# NMX-201.net
KiCad netlist of a schematic drawn in EAGLE
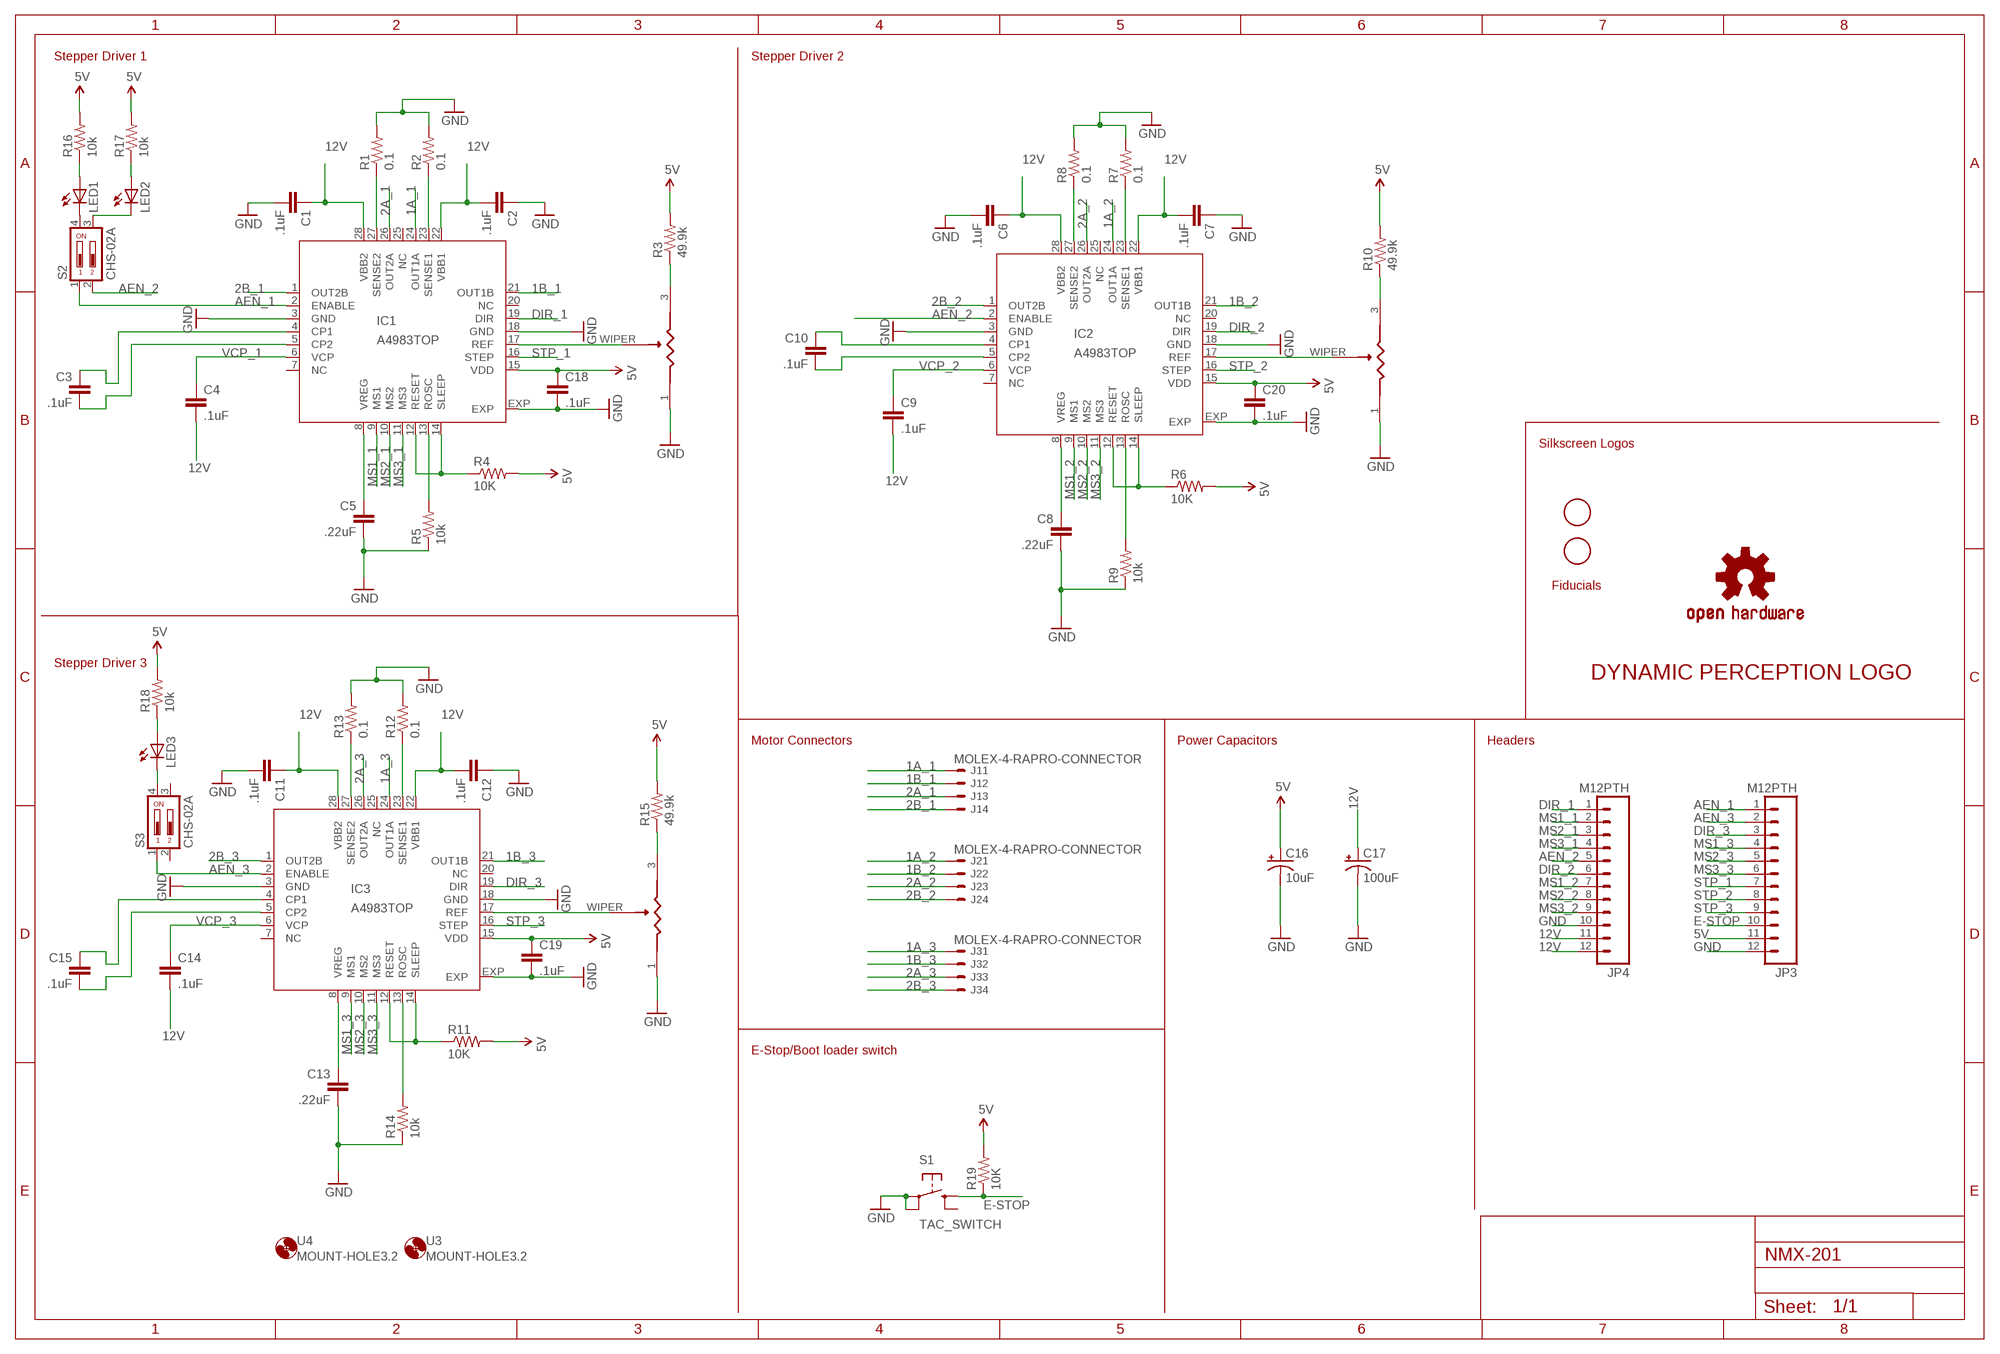
[diagram p0: schematic, sheet 1]

(export (version "E")
  (design (tool "Eeschema 10.0.6"))
  (components
    (comp (ref "C1")
      (value ".1uF")
      (footprint "eagle-import:0402-CAP")
      (fields (field (name "MF") "Taiyo Yuden") (field (name "MPN") "TMK105BJ104KV-F"))
      (libsource (lib "eagle-import") (part "CAP0402-CAP"))
    )
    (comp (ref "C2")
      (value ".1uF")
      (footprint "eagle-import:0402-CAP")
      (fields (field (name "MF") "Taiyo Yuden") (field (name "MPN") "TMK105BJ104KV-F"))
      (libsource (lib "eagle-import") (part "CAP0402-CAP"))
    )
    (comp (ref "C3")
      (value ".1uF")
      (footprint "eagle-import:0402-CAP")
      (fields (field (name "MF") "Taiyo Yuden") (field (name "MPN") "TMK105BJ104KV-F"))
      (libsource (lib "eagle-import") (part "CAP0402-CAP"))
    )
    (comp (ref "C4")
      (value ".1uF")
      (footprint "eagle-import:0402-CAP")
      (fields (field (name "MF") "Taiyo Yuden") (field (name "MPN") "TMK105BJ104KV-F"))
      (libsource (lib "eagle-import") (part "CAP0402-CAP"))
    )
    (comp (ref "C5")
      (value ".22uF")
      (footprint "eagle-import:0402-CAP")
      (fields (field (name "MF") "Taiyo Yuden") (field (name "MPN") "TMK105BJ224KVHF"))
      (libsource (lib "eagle-import") (part "CAP0402-CAP"))
    )
    (comp (ref "C6")
      (value ".1uF")
      (footprint "eagle-import:0402-CAP")
      (fields (field (name "MF") "Taiyo Yuden") (field (name "MPN") "TMK105BJ104KV-F"))
      (libsource (lib "eagle-import") (part "CAP0402-CAP"))
    )
    (comp (ref "C7")
      (value ".1uF")
      (footprint "eagle-import:0402-CAP")
      (fields (field (name "MF") "Taiyo Yuden") (field (name "MPN") "TMK105BJ104KV-F"))
      (libsource (lib "eagle-import") (part "CAP0402-CAP"))
    )
    (comp (ref "C8")
      (value ".22uF")
      (footprint "eagle-import:0402-CAP")
      (fields (field (name "MF") "Taiyo Yuden") (field (name "MPN") "TMK105BJ224KVHF"))
      (libsource (lib "eagle-import") (part "CAP0402-CAP"))
    )
    (comp (ref "C9")
      (value ".1uF")
      (footprint "eagle-import:0402-CAP")
      (fields (field (name "MF") "Taiyo Yuden") (field (name "MPN") "TMK105BJ104KV-F"))
      (libsource (lib "eagle-import") (part "CAP0402-CAP"))
    )
    (comp (ref "C10")
      (value ".1uF")
      (footprint "eagle-import:0402-CAP")
      (fields (field (name "MF") "Taiyo Yuden") (field (name "MPN") "TMK105BJ104KV-F"))
      (libsource (lib "eagle-import") (part "CAP0402-CAP"))
    )
    (comp (ref "C11")
      (value ".1uF")
      (footprint "eagle-import:0402-CAP")
      (fields (field (name "MF") "Taiyo Yuden") (field (name "MPN") "TMK105BJ104KV-F"))
      (libsource (lib "eagle-import") (part "CAP0402-CAP"))
    )
    (comp (ref "C12")
      (value ".1uF")
      (footprint "eagle-import:0402-CAP")
      (fields (field (name "MF") "Taiyo Yuden") (field (name "MPN") "TMK105BJ104KV-F"))
      (libsource (lib "eagle-import") (part "CAP0402-CAP"))
    )
    (comp (ref "C13")
      (value ".22uF")
      (footprint "eagle-import:0402-CAP")
      (fields (field (name "MF") "Taiyo Yuden") (field (name "MPN") "TMK105BJ224KVHF"))
      (libsource (lib "eagle-import") (part "CAP0402-CAP"))
    )
    (comp (ref "C14")
      (value ".1uF")
      (footprint "eagle-import:0402-CAP")
      (fields (field (name "MF") "Taiyo Yuden") (field (name "MPN") "TMK105BJ104KV-F"))
      (libsource (lib "eagle-import") (part "CAP0402-CAP"))
    )
    (comp (ref "C15")
      (value ".1uF")
      (footprint "eagle-import:0402-CAP")
      (fields (field (name "MF") "Taiyo Yuden") (field (name "MPN") "TMK105BJ104KV-F"))
      (libsource (lib "eagle-import") (part "CAP0402-CAP"))
    )
    (comp (ref "C16")
      (value "10uF")
      (footprint "eagle-import:EIA3216")
      (fields (field (name "MF") "Kemet") (field (name "MPN") "T491A106M016AT"))
      (libsource (lib "eagle-import") (part "CAP_POL1206"))
    )
    (comp (ref "C17")
      (value "100uF")
      (footprint "eagle-import:PANASONIC_D")
      (fields (field (name "MF") "Panasonic Electronic Components") (field (name "MPN") "EEE-1EA101XP"))
      (libsource (lib "eagle-import") (part "CAP_POLD"))
    )
    (comp (ref "C18")
      (value ".1uF")
      (footprint "eagle-import:0402-CAP")
      (fields (field (name "MF") "Taiyo Yuden") (field (name "MPN") "TMK105BJ104KV-F"))
      (libsource (lib "eagle-import") (part "CAP0402-CAP"))
    )
    (comp (ref "C19")
      (value ".1uF")
      (footprint "eagle-import:0402-CAP")
      (fields (field (name "MF") "Taiyo Yuden") (field (name "MPN") "TMK105BJ104KV-F"))
      (libsource (lib "eagle-import") (part "CAP0402-CAP"))
    )
    (comp (ref "C20")
      (value ".1uF")
      (footprint "eagle-import:0402-CAP")
      (fields (field (name "MF") "Taiyo Yuden") (field (name "MPN") "TMK105BJ104KV-F"))
      (libsource (lib "eagle-import") (part "CAP0402-CAP"))
    )
    (comp (ref "FRAME2")
      (value "A3L-LOCSILK_SCREEN")
      (footprint "eagle-import:DRAWING_NAME")
      (libsource (lib "eagle-import") (part "A3L-LOCSILK_SCREEN"))
    )
    (comp (ref "IC1")
      (value "A4983TOP")
      (footprint "eagle-import:QFN28ET")
      (fields (field (name "MPN") "A4983SETTR-T") (field (name "MPN_1") "A4983SETTR-T"))
      (libsource (lib "eagle-import") (part "A4983TOP"))
    )
    (comp (ref "IC2")
      (value "A4983TOP")
      (footprint "eagle-import:QFN28ET")
      (fields (field (name "MPN") "A4983SETTR-T") (field (name "MPN_1") "A4983SETTR-T"))
      (libsource (lib "eagle-import") (part "A4983TOP"))
    )
    (comp (ref "IC3")
      (value "A4983TOP")
      (footprint "eagle-import:QFN28ET")
      (fields (field (name "MPN") "A4983SETTR-T") (field (name "MPN_1") "A4983SETTR-T"))
      (libsource (lib "eagle-import") (part "A4983TOP"))
    )
    (comp (ref "J1")
      (value "MOLEX-4-RAPRO-CONNECTOR")
      (footprint "eagle-import:PRO_CONNECTOR")
      (fields (field (name "MF") "Molex Inc") (field (name "MPN") "0022053041"))
      (libsource (lib "eagle-import") (part "MOLEX-4-RAPRO-CONNECTOR"))
    )
    (comp (ref "J2")
      (value "MOLEX-4-RAPRO-CONNECTOR")
      (footprint "eagle-import:PRO_CONNECTOR")
      (fields (field (name "MF") "Molex Inc") (field (name "MPN") "0022053041"))
      (libsource (lib "eagle-import") (part "MOLEX-4-RAPRO-CONNECTOR"))
    )
    (comp (ref "J3")
      (value "MOLEX-4-RAPRO-CONNECTOR")
      (footprint "eagle-import:PRO_CONNECTOR")
      (fields (field (name "MF") "Molex Inc") (field (name "MPN") "0022053041"))
      (libsource (lib "eagle-import") (part "MOLEX-4-RAPRO-CONNECTOR"))
    )
    (comp (ref "JP3")
      (value "M12PTH")
      (footprint "eagle-import:1X12")
      (fields (field (name "MF") "Molex Inc") (field (name "MPN") "0901200132"))
      (libsource (lib "eagle-import") (part "M12PTH"))
    )
    (comp (ref "JP4")
      (value "M12PTH")
      (footprint "eagle-import:1X12")
      (fields (field (name "MF") "Molex Inc") (field (name "MPN") "0901200132"))
      (libsource (lib "eagle-import") (part "M12PTH"))
    )
    (comp (ref "LED1")
      (value "LED0603")
      (footprint "eagle-import:LED-0603")
      (fields (field (name "MF") "OSRAM Opto Semiconductors Inc") (field (name "MPN") "LB Q39G-L2N2-35-1"))
      (libsource (lib "eagle-import") (part "LED0603"))
    )
    (comp (ref "LED2")
      (value "LED0603")
      (footprint "eagle-import:LED-0603")
      (fields (field (name "MF") "OSRAM Opto Semiconductors Inc") (field (name "MPN") "LB Q39G-L2N2-35-1"))
      (libsource (lib "eagle-import") (part "LED0603"))
    )
    (comp (ref "LED3")
      (value "LED0603")
      (footprint "eagle-import:LED-0603")
      (fields (field (name "MF") "OSRAM Opto Semiconductors Inc") (field (name "MPN") "LB Q39G-L2N2-35-1"))
      (libsource (lib "eagle-import") (part "LED0603"))
    )
    (comp (ref "R1")
      (value "0.1")
      (footprint "eagle-import:R0603")
      (fields (field (name "MF") "Samsung Electro-Mechanics America") (field (name "MPN") "RU1608FR100CS"))
      (libsource (lib "eagle-import") (part "R-US_R0603"))
    )
    (comp (ref "R2")
      (value "0.1")
      (footprint "eagle-import:R0603")
      (fields (field (name "MF") "Samsung Electro-Mechanics America") (field (name "MPN") "RU1608FR100CS"))
      (libsource (lib "eagle-import") (part "R-US_R0603"))
    )
    (comp (ref "R3")
      (value "49.9k")
      (footprint "eagle-import:R0402_BOTTOM")
      (fields (field (name "MF") "Yageo") (field (name "MPN") "RC0402FR-0749K9L"))
      (libsource (lib "eagle-import") (part "R-US_R0402_B"))
    )
    (comp (ref "R4")
      (value "10K")
      (footprint "eagle-import:R0402_BOTTOM")
      (fields (field (name "MF") "Yageo") (field (name "MPN") "RC0402FR-0710KL"))
      (libsource (lib "eagle-import") (part "R-US_R0402_B"))
    )
    (comp (ref "R5")
      (value "10k")
      (footprint "eagle-import:R0402_BOTTOM")
      (fields (field (name "MF") "Yageo") (field (name "MPN") "RC0402FR-0720KL"))
      (libsource (lib "eagle-import") (part "R-US_R0402_B"))
    )
    (comp (ref "R6")
      (value "10K")
      (footprint "eagle-import:R0402_BOTTOM")
      (fields (field (name "MF") "Yageo") (field (name "MPN") "RC0402FR-0710KL"))
      (libsource (lib "eagle-import") (part "R-US_R0402_B"))
    )
    (comp (ref "R7")
      (value "0.1")
      (footprint "eagle-import:R0603")
      (fields (field (name "MF") "Samsung Electro-Mechanics America") (field (name "MPN") "RU1608FR100CS"))
      (libsource (lib "eagle-import") (part "R-US_R0603"))
    )
    (comp (ref "R8")
      (value "0.1")
      (footprint "eagle-import:R0603")
      (fields (field (name "MF") "Samsung Electro-Mechanics America") (field (name "MPN") "RU1608FR100CS"))
      (libsource (lib "eagle-import") (part "R-US_R0603"))
    )
    (comp (ref "R9")
      (value "10k")
      (footprint "eagle-import:R0402_BOTTOM")
      (fields (field (name "MF") "Yageo") (field (name "MPN") "RC0402FR-0720KL"))
      (libsource (lib "eagle-import") (part "R-US_R0402_B"))
    )
    (comp (ref "R10")
      (value "49.9k")
      (footprint "eagle-import:R0402_BOTTOM")
      (fields (field (name "MF") "Yageo") (field (name "MPN") "RC0402FR-0749K9L"))
      (libsource (lib "eagle-import") (part "R-US_R0402_B"))
    )
    (comp (ref "R11")
      (value "10K")
      (footprint "eagle-import:R0402_BOTTOM")
      (fields (field (name "MF") "Yageo") (field (name "MPN") "RC0402FR-0710KL"))
      (libsource (lib "eagle-import") (part "R-US_R0402_B"))
    )
    (comp (ref "R12")
      (value "0.1")
      (footprint "eagle-import:R0603")
      (fields (field (name "MF") "Samsung Electro-Mechanics America") (field (name "MPN") "RU1608FR100CS"))
      (libsource (lib "eagle-import") (part "R-US_R0603"))
    )
    (comp (ref "R13")
      (value "0.1")
      (footprint "eagle-import:R0603")
      (fields (field (name "MF") "Samsung Electro-Mechanics America") (field (name "MPN") "RU1608FR100CS"))
      (libsource (lib "eagle-import") (part "R-US_R0603"))
    )
    (comp (ref "R14")
      (value "10k")
      (footprint "eagle-import:R0402_BOTTOM")
      (fields (field (name "MF") "Yageo") (field (name "MPN") "RC0402FR-0720KL"))
      (libsource (lib "eagle-import") (part "R-US_R0402_B"))
    )
    (comp (ref "R15")
      (value "49.9k")
      (footprint "eagle-import:R0402_BOTTOM")
      (fields (field (name "MF") "Yageo") (field (name "MPN") "RC0402FR-0749K9L"))
      (libsource (lib "eagle-import") (part "R-US_R0402_B"))
    )
    (comp (ref "R16")
      (value "10k")
      (footprint "eagle-import:R0402_BOTTOM")
      (fields (field (name "MF") "Yageo") (field (name "MPN") "RC0402FR-0714KL"))
      (libsource (lib "eagle-import") (part "R-US_R0402_B"))
    )
    (comp (ref "R17")
      (value "10k")
      (footprint "eagle-import:R0402_BOTTOM")
      (fields (field (name "MF") "Yageo") (field (name "MPN") "RC0402FR-0714KL"))
      (libsource (lib "eagle-import") (part "R-US_R0402_B"))
    )
    (comp (ref "R18")
      (value "10k")
      (footprint "eagle-import:R0402_BOTTOM")
      (fields (field (name "MF") "Yageo") (field (name "MPN") "RC0402FR-0714KL"))
      (libsource (lib "eagle-import") (part "R-US_R0402_B"))
    )
    (comp (ref "R19")
      (value "10K")
      (footprint "eagle-import:R0402_BOTTOM")
      (fields (field (name "MF") "Yageo") (field (name "MPN") "RC0402FR-0710KL"))
      (libsource (lib "eagle-import") (part "R-US_R0402_B"))
    )
    (comp (ref "S1")
      (value "TAC_SWITCH")
      (footprint "eagle-import:TAC_SWITCH_THR")
      (fields (field (name "MF") "TE Connectivity") (field (name "MPN") "2-1825027-0"))
      (libsource (lib "eagle-import") (part "TAC_SWITCH"))
    )
    (comp (ref "S2")
      (value "CHS-02A")
      (footprint "eagle-import:CHS-02A")
      (libsource (lib "eagle-import") (part "CHS-02A"))
    )
    (comp (ref "S3")
      (value "CHS-02A")
      (footprint "eagle-import:CHS-02A")
      (libsource (lib "eagle-import") (part "CHS-02A"))
    )
    (comp (ref "U$1")
      (value "DP_LOGOMICRO")
      (footprint "eagle-import:DP_LOGO_MICRO")
      (libsource (lib "eagle-import") (part "DP_LOGOMICRO"))
    )
    (comp (ref "U$2")
      (value "OSHW-LOGOS")
      (footprint "eagle-import:OSHW-LOGO-S")
      (libsource (lib "eagle-import") (part "OSHW-LOGOS"))
    )
    (comp (ref "U$3")
      (value "FIDUCIAL")
      (footprint "eagle-import:FIDUCIAL_1MM")
      (libsource (lib "eagle-import") (part "FIDUCIAL"))
    )
    (comp (ref "U$4")
      (value "FIDUCIAL")
      (footprint "eagle-import:FIDUCIAL_1MM")
      (libsource (lib "eagle-import") (part "FIDUCIAL"))
    )
    (comp (ref "U1")
      (value "CADJ")
      (footprint "eagle-import:3MM_SMD")
      (fields (field (name "MF") "Bourns Inc") (field (name "MPN") "TC33X-2-103E"))
      (libsource (lib "eagle-import") (part "TC33X-2"))
    )
    (comp (ref "U2")
      (value "CADJ")
      (footprint "eagle-import:3MM_SMD")
      (fields (field (name "MF") "Bourns Inc") (field (name "MPN") "TC33X-2-103E"))
      (libsource (lib "eagle-import") (part "TC33X-2"))
    )
    (comp (ref "U3")
      (value "MOUNT-HOLE3.2")
      (footprint "eagle-import:3,2")
      (libsource (lib "eagle-import") (part "MOUNT-HOLE3.2"))
    )
    (comp (ref "U4")
      (value "MOUNT-HOLE3.2")
      (footprint "eagle-import:3,2")
      (libsource (lib "eagle-import") (part "MOUNT-HOLE3.2"))
    )
    (comp (ref "U5")
      (value "CADJ")
      (footprint "eagle-import:3MM_SMD")
      (fields (field (name "MF") "Bourns Inc") (field (name "MPN") "TC33X-2-103E"))
      (libsource (lib "eagle-import") (part "TC33X-2"))
    )
  )
  (nets
    (net (code "1") (name "/1A_1") (class "Default")
      (node (ref "IC1") (pin "24") (pinfunction "OUT1A_24") (pintype "output"))
      (node (ref "J1") (pin "P$1") (pinfunction "S_P$1") (pintype "passive"))
    )
    (net (code "2") (name "/1A_2") (class "Default")
      (node (ref "IC2") (pin "24") (pinfunction "OUT1A_24") (pintype "output"))
      (node (ref "J2") (pin "P$1") (pinfunction "S_P$1") (pintype "passive"))
    )
    (net (code "3") (name "/1A_3") (class "Default")
      (node (ref "IC3") (pin "24") (pinfunction "OUT1A_24") (pintype "output"))
      (node (ref "J3") (pin "P$1") (pinfunction "S_P$1") (pintype "passive"))
    )
    (net (code "4") (name "/1B_1") (class "Default")
      (node (ref "IC1") (pin "21") (pinfunction "OUT1B_21") (pintype "output"))
      (node (ref "J1") (pin "P$2") (pinfunction "S_P$2") (pintype "passive"))
    )
    (net (code "5") (name "/1B_2") (class "Default")
      (node (ref "IC2") (pin "21") (pinfunction "OUT1B_21") (pintype "output"))
      (node (ref "J2") (pin "P$2") (pinfunction "S_P$2") (pintype "passive"))
    )
    (net (code "6") (name "/1B_3") (class "Default")
      (node (ref "IC3") (pin "21") (pinfunction "OUT1B_21") (pintype "output"))
      (node (ref "J3") (pin "P$2") (pinfunction "S_P$2") (pintype "passive"))
    )
    (net (code "7") (name "/2A_1") (class "Default")
      (node (ref "IC1") (pin "26") (pinfunction "OUT2A_26") (pintype "output"))
      (node (ref "J1") (pin "P$3") (pinfunction "S_P$3") (pintype "passive"))
    )
    (net (code "8") (name "/2A_2") (class "Default")
      (node (ref "IC2") (pin "26") (pinfunction "OUT2A_26") (pintype "output"))
      (node (ref "J2") (pin "P$3") (pinfunction "S_P$3") (pintype "passive"))
    )
    (net (code "9") (name "/2A_3") (class "Default")
      (node (ref "IC3") (pin "26") (pinfunction "OUT2A_26") (pintype "output"))
      (node (ref "J3") (pin "P$3") (pinfunction "S_P$3") (pintype "passive"))
    )
    (net (code "10") (name "/2B_1") (class "Default")
      (node (ref "IC1") (pin "1") (pinfunction "OUT2B_1") (pintype "output"))
      (node (ref "J1") (pin "P$4") (pinfunction "S_P$4") (pintype "passive"))
    )
    (net (code "11") (name "/2B_2") (class "Default")
      (node (ref "IC2") (pin "1") (pinfunction "OUT2B_1") (pintype "output"))
      (node (ref "J2") (pin "P$4") (pinfunction "S_P$4") (pintype "passive"))
    )
    (net (code "12") (name "/2B_3") (class "Default")
      (node (ref "IC3") (pin "1") (pinfunction "OUT2B_1") (pintype "output"))
      (node (ref "J3") (pin "P$4") (pinfunction "S_P$4") (pintype "passive"))
    )
    (net (code "13") (name "/12V") (class "Default")
      (node (ref "C1") (pin "1") (pinfunction "1_1") (pintype "passive"))
      (node (ref "C11") (pin "1") (pinfunction "1_1") (pintype "passive"))
      (node (ref "C12") (pin "2") (pinfunction "2_2") (pintype "passive"))
      (node (ref "C14") (pin "2") (pinfunction "2_2") (pintype "passive"))
      (node (ref "C17") (pin "+") (pinfunction "+_+") (pintype "passive"))
      (node (ref "C2") (pin "2") (pinfunction "2_2") (pintype "passive"))
      (node (ref "C4") (pin "2") (pinfunction "2_2") (pintype "passive"))
      (node (ref "C6") (pin "1") (pinfunction "1_1") (pintype "passive"))
      (node (ref "C7") (pin "2") (pinfunction "2_2") (pintype "passive"))
      (node (ref "C9") (pin "2") (pinfunction "2_2") (pintype "passive"))
      (node (ref "IC1") (pin "22") (pinfunction "VBB1_22") (pintype "power_in"))
      (node (ref "IC1") (pin "28") (pinfunction "VBB2_28") (pintype "power_in"))
      (node (ref "IC2") (pin "22") (pinfunction "VBB1_22") (pintype "power_in"))
      (node (ref "IC2") (pin "28") (pinfunction "VBB2_28") (pintype "power_in"))
      (node (ref "IC3") (pin "22") (pinfunction "VBB1_22") (pintype "power_in"))
      (node (ref "IC3") (pin "28") (pinfunction "VBB2_28") (pintype "power_in"))
      (node (ref "JP4") (pin "11") (pinfunction "11_11") (pintype "passive"))
      (node (ref "JP4") (pin "12") (pinfunction "12_12") (pintype "passive"))
    )
    (net (code "14") (name "/AEN_1") (class "Default")
      (node (ref "IC1") (pin "2") (pinfunction "ENABLE_2") (pintype "input"))
      (node (ref "JP3") (pin "1") (pinfunction "1_1") (pintype "passive"))
      (node (ref "S2") (pin "1") (pinfunction "1_1") (pintype "passive"))
    )
    (net (code "15") (name "/AEN_2") (class "Default")
      (node (ref "IC2") (pin "2") (pinfunction "ENABLE_2") (pintype "input"))
      (node (ref "JP4") (pin "5") (pinfunction "5_5") (pintype "passive"))
      (node (ref "S2") (pin "2") (pinfunction "2_2") (pintype "passive"))
    )
    (net (code "16") (name "/AEN_3") (class "Default")
      (node (ref "IC3") (pin "2") (pinfunction "ENABLE_2") (pintype "input"))
      (node (ref "JP3") (pin "2") (pinfunction "2_2") (pintype "passive"))
      (node (ref "S3") (pin "1") (pinfunction "1_1") (pintype "passive"))
    )
    (net (code "17") (name "/DIR_1") (class "Default")
      (node (ref "IC1") (pin "19") (pinfunction "DIR_19") (pintype "input"))
      (node (ref "JP4") (pin "1") (pinfunction "1_1") (pintype "passive"))
    )
    (net (code "18") (name "/DIR_2") (class "Default")
      (node (ref "IC2") (pin "19") (pinfunction "DIR_19") (pintype "input"))
      (node (ref "JP4") (pin "6") (pinfunction "6_6") (pintype "passive"))
    )
    (net (code "19") (name "/DIR_3") (class "Default")
      (node (ref "IC3") (pin "19") (pinfunction "DIR_19") (pintype "input"))
      (node (ref "JP3") (pin "3") (pinfunction "3_3") (pintype "passive"))
    )
    (net (code "20") (name "/E-STOP") (class "Default")
      (node (ref "JP3") (pin "10") (pinfunction "10_10") (pintype "passive"))
      (node (ref "R19") (pin "1") (pinfunction "1_1") (pintype "passive"))
      (node (ref "S1") (pin "B") (pinfunction "3_B") (pintype "passive"))
    )
    (net (code "21") (name "/MS1_1") (class "Default")
      (node (ref "IC1") (pin "9") (pinfunction "MS1_9") (pintype "input"))
      (node (ref "JP4") (pin "2") (pinfunction "2_2") (pintype "passive"))
    )
    (net (code "22") (name "/MS1_2") (class "Default")
      (node (ref "IC2") (pin "9") (pinfunction "MS1_9") (pintype "input"))
      (node (ref "JP4") (pin "7") (pinfunction "7_7") (pintype "passive"))
    )
    (net (code "23") (name "/MS1_3") (class "Default")
      (node (ref "IC3") (pin "9") (pinfunction "MS1_9") (pintype "input"))
      (node (ref "JP3") (pin "4") (pinfunction "4_4") (pintype "passive"))
    )
    (net (code "24") (name "/MS2_1") (class "Default")
      (node (ref "IC1") (pin "10") (pinfunction "MS2_10") (pintype "input"))
      (node (ref "JP4") (pin "3") (pinfunction "3_3") (pintype "passive"))
    )
    (net (code "25") (name "/MS2_2") (class "Default")
      (node (ref "IC2") (pin "10") (pinfunction "MS2_10") (pintype "input"))
      (node (ref "JP4") (pin "8") (pinfunction "8_8") (pintype "passive"))
    )
    (net (code "26") (name "/MS2_3") (class "Default")
      (node (ref "IC3") (pin "10") (pinfunction "MS2_10") (pintype "input"))
      (node (ref "JP3") (pin "5") (pinfunction "5_5") (pintype "passive"))
    )
    (net (code "27") (name "/MS3_1") (class "Default")
      (node (ref "IC1") (pin "11") (pinfunction "MS3_11") (pintype "input"))
      (node (ref "JP4") (pin "4") (pinfunction "4_4") (pintype "passive"))
    )
    (net (code "28") (name "/MS3_2") (class "Default")
      (node (ref "IC2") (pin "11") (pinfunction "MS3_11") (pintype "input"))
      (node (ref "JP4") (pin "9") (pinfunction "9_9") (pintype "passive"))
    )
    (net (code "29") (name "/MS3_3") (class "Default")
      (node (ref "IC3") (pin "11") (pinfunction "MS3_11") (pintype "input"))
      (node (ref "JP3") (pin "6") (pinfunction "6_6") (pintype "passive"))
    )
    (net (code "30") (name "/STP_1") (class "Default")
      (node (ref "IC1") (pin "16") (pinfunction "STEP_16") (pintype "input"))
      (node (ref "JP3") (pin "7") (pinfunction "7_7") (pintype "passive"))
    )
    (net (code "31") (name "/STP_2") (class "Default")
      (node (ref "IC2") (pin "16") (pinfunction "STEP_16") (pintype "input"))
      (node (ref "JP3") (pin "8") (pinfunction "8_8") (pintype "passive"))
    )
    (net (code "32") (name "/STP_3") (class "Default")
      (node (ref "IC3") (pin "16") (pinfunction "STEP_16") (pintype "input"))
      (node (ref "JP3") (pin "9") (pinfunction "9_9") (pintype "passive"))
    )
    (net (code "33") (name "/VCP_1") (class "Default")
      (node (ref "C4") (pin "1") (pinfunction "1_1") (pintype "passive"))
      (node (ref "IC1") (pin "6") (pinfunction "VCP_6") (pintype "passive"))
    )
    (net (code "34") (name "/VCP_2") (class "Default")
      (node (ref "C9") (pin "1") (pinfunction "1_1") (pintype "passive"))
      (node (ref "IC2") (pin "6") (pinfunction "VCP_6") (pintype "passive"))
    )
    (net (code "35") (name "/VCP_3") (class "Default")
      (node (ref "C14") (pin "1") (pinfunction "1_1") (pintype "passive"))
      (node (ref "IC3") (pin "6") (pinfunction "VCP_6") (pintype "passive"))
    )
    (net (code "36") (name "5V") (class "Default")
      (node (ref "C16") (pin "A") (pinfunction "+_A") (pintype "passive"))
      (node (ref "C18") (pin "1") (pinfunction "1_1") (pintype "passive"))
      (node (ref "C19") (pin "1") (pinfunction "1_1") (pintype "passive"))
      (node (ref "C20") (pin "1") (pinfunction "1_1") (pintype "passive"))
      (node (ref "IC1") (pin "15") (pinfunction "VDD_15") (pintype "power_in"))
      (node (ref "IC2") (pin "15") (pinfunction "VDD_15") (pintype "power_in"))
      (node (ref "IC3") (pin "15") (pinfunction "VDD_15") (pintype "power_in"))
      (node (ref "JP3") (pin "11") (pinfunction "11_11") (pintype "passive"))
      (node (ref "R10") (pin "2") (pinfunction "2_2") (pintype "passive"))
      (node (ref "R11") (pin "2") (pinfunction "2_2") (pintype "passive"))
      (node (ref "R15") (pin "2") (pinfunction "2_2") (pintype "passive"))
      (node (ref "R16") (pin "2") (pinfunction "2_2") (pintype "passive"))
      (node (ref "R17") (pin "2") (pinfunction "2_2") (pintype "passive"))
      (node (ref "R18") (pin "2") (pinfunction "2_2") (pintype "passive"))
      (node (ref "R19") (pin "2") (pinfunction "2_2") (pintype "passive"))
      (node (ref "R3") (pin "2") (pinfunction "2_2") (pintype "passive"))
      (node (ref "R4") (pin "2") (pinfunction "2_2") (pintype "passive"))
      (node (ref "R6") (pin "2") (pinfunction "2_2") (pintype "passive"))
    )
    (net (code "37") (name "GND") (class "Default")
      (node (ref "C1") (pin "2") (pinfunction "2_2") (pintype "passive"))
      (node (ref "C11") (pin "2") (pinfunction "2_2") (pintype "passive"))
      (node (ref "C12") (pin "1") (pinfunction "1_1") (pintype "passive"))
      (node (ref "C13") (pin "2") (pinfunction "2_2") (pintype "passive"))
      (node (ref "C16") (pin "C") (pinfunction "-_C") (pintype "passive"))
      (node (ref "C17") (pin "-") (pinfunction "-_-") (pintype "passive"))
      (node (ref "C18") (pin "2") (pinfunction "2_2") (pintype "passive"))
      (node (ref "C19") (pin "2") (pinfunction "2_2") (pintype "passive"))
      (node (ref "C2") (pin "1") (pinfunction "1_1") (pintype "passive"))
      (node (ref "C20") (pin "2") (pinfunction "2_2") (pintype "passive"))
      (node (ref "C5") (pin "2") (pinfunction "2_2") (pintype "passive"))
      (node (ref "C6") (pin "2") (pinfunction "2_2") (pintype "passive"))
      (node (ref "C7") (pin "1") (pinfunction "1_1") (pintype "passive"))
      (node (ref "C8") (pin "2") (pinfunction "2_2") (pintype "passive"))
      (node (ref "IC1") (pin "18") (pinfunction "GND_18") (pintype "power_in"))
      (node (ref "IC1") (pin "3") (pinfunction "GND_3") (pintype "power_in"))
      (node (ref "IC1") (pin "EXP") (pinfunction "EXP_EXP") (pintype "passive"))
      (node (ref "IC2") (pin "18") (pinfunction "GND_18") (pintype "power_in"))
      (node (ref "IC2") (pin "3") (pinfunction "GND_3") (pintype "power_in"))
      (node (ref "IC2") (pin "EXP") (pinfunction "EXP_EXP") (pintype "passive"))
      (node (ref "IC3") (pin "18") (pinfunction "GND_18") (pintype "power_in"))
      (node (ref "IC3") (pin "3") (pinfunction "GND_3") (pintype "power_in"))
      (node (ref "IC3") (pin "EXP") (pinfunction "EXP_EXP") (pintype "passive"))
      (node (ref "JP3") (pin "12") (pinfunction "12_12") (pintype "passive"))
      (node (ref "JP4") (pin "10") (pinfunction "10_10") (pintype "passive"))
      (node (ref "R1") (pin "2") (pinfunction "2_2") (pintype "passive"))
      (node (ref "R12") (pin "2") (pinfunction "2_2") (pintype "passive"))
      (node (ref "R13") (pin "2") (pinfunction "2_2") (pintype "passive"))
      (node (ref "R14") (pin "1") (pinfunction "1_1") (pintype "passive"))
      (node (ref "R2") (pin "2") (pinfunction "2_2") (pintype "passive"))
      (node (ref "R5") (pin "1") (pinfunction "1_1") (pintype "passive"))
      (node (ref "R7") (pin "2") (pinfunction "2_2") (pintype "passive"))
      (node (ref "R8") (pin "2") (pinfunction "2_2") (pintype "passive"))
      (node (ref "R9") (pin "1") (pinfunction "1_1") (pintype "passive"))
      (node (ref "S1") (pin "A") (pinfunction "1_A") (pintype "passive"))
      (node (ref "S1") (pin "P$1") (pinfunction "2_P$1") (pintype "passive"))
      (node (ref "U1") (pin "1") (pinfunction "1_1") (pintype "bidirectional"))
      (node (ref "U2") (pin "1") (pinfunction "1_1") (pintype "bidirectional"))
      (node (ref "U5") (pin "1") (pinfunction "1_1") (pintype "bidirectional"))
    )
    (net (code "38") (name "Net-(IC1-CP1)") (class "Default")
      (node (ref "C3") (pin "1") (pinfunction "1_1") (pintype "passive"))
      (node (ref "IC1") (pin "4") (pinfunction "CP1_4") (pintype "passive"))
    )
    (net (code "39") (name "Net-(IC1-CP2)") (class "Default")
      (node (ref "C3") (pin "2") (pinfunction "2_2") (pintype "passive"))
      (node (ref "IC1") (pin "5") (pinfunction "CP2_5") (pintype "passive"))
    )
    (net (code "40") (name "Net-(IC1-REF)") (class "Default")
      (node (ref "IC1") (pin "17") (pinfunction "REF_17") (pintype "input"))
      (node (ref "U1") (pin "WIPER") (pinfunction "2_WIPER") (pintype "bidirectional"))
    )
    (net (code "41") (name "Net-(IC1-RESET)") (class "Default")
      (node (ref "IC1") (pin "12") (pinfunction "RESET_12") (pintype "input"))
      (node (ref "IC1") (pin "14") (pinfunction "SLEEP_14") (pintype "input"))
      (node (ref "R4") (pin "1") (pinfunction "1_1") (pintype "passive"))
    )
    (net (code "42") (name "Net-(IC1-ROSC)") (class "Default")
      (node (ref "IC1") (pin "13") (pinfunction "ROSC_13") (pintype "input"))
      (node (ref "R5") (pin "2") (pinfunction "2_2") (pintype "passive"))
    )
    (net (code "43") (name "Net-(IC1-SENSE1)") (class "Default")
      (node (ref "IC1") (pin "23") (pinfunction "SENSE1_23") (pintype "input"))
      (node (ref "R2") (pin "1") (pinfunction "1_1") (pintype "passive"))
    )
    (net (code "44") (name "Net-(IC1-SENSE2)") (class "Default")
      (node (ref "IC1") (pin "27") (pinfunction "SENSE2_27") (pintype "input"))
      (node (ref "R1") (pin "1") (pinfunction "1_1") (pintype "passive"))
    )
    (net (code "45") (name "Net-(IC1-VREG)") (class "Default")
      (node (ref "C5") (pin "1") (pinfunction "1_1") (pintype "passive"))
      (node (ref "IC1") (pin "8") (pinfunction "VREG_8") (pintype "passive"))
    )
    (net (code "46") (name "Net-(IC2-CP1)") (class "Default")
      (node (ref "C10") (pin "1") (pinfunction "1_1") (pintype "passive"))
      (node (ref "IC2") (pin "4") (pinfunction "CP1_4") (pintype "passive"))
    )
    (net (code "47") (name "Net-(IC2-CP2)") (class "Default")
      (node (ref "C10") (pin "2") (pinfunction "2_2") (pintype "passive"))
      (node (ref "IC2") (pin "5") (pinfunction "CP2_5") (pintype "passive"))
    )
    (net (code "48") (name "Net-(IC2-REF)") (class "Default")
      (node (ref "IC2") (pin "17") (pinfunction "REF_17") (pintype "input"))
      (node (ref "U2") (pin "WIPER") (pinfunction "2_WIPER") (pintype "bidirectional"))
    )
    (net (code "49") (name "Net-(IC2-RESET)") (class "Default")
      (node (ref "IC2") (pin "12") (pinfunction "RESET_12") (pintype "input"))
      (node (ref "IC2") (pin "14") (pinfunction "SLEEP_14") (pintype "input"))
      (node (ref "R6") (pin "1") (pinfunction "1_1") (pintype "passive"))
    )
    (net (code "50") (name "Net-(IC2-ROSC)") (class "Default")
      (node (ref "IC2") (pin "13") (pinfunction "ROSC_13") (pintype "input"))
      (node (ref "R9") (pin "2") (pinfunction "2_2") (pintype "passive"))
    )
    (net (code "51") (name "Net-(IC2-SENSE1)") (class "Default")
      (node (ref "IC2") (pin "23") (pinfunction "SENSE1_23") (pintype "input"))
      (node (ref "R7") (pin "1") (pinfunction "1_1") (pintype "passive"))
    )
    (net (code "52") (name "Net-(IC2-SENSE2)") (class "Default")
      (node (ref "IC2") (pin "27") (pinfunction "SENSE2_27") (pintype "input"))
      (node (ref "R8") (pin "1") (pinfunction "1_1") (pintype "passive"))
    )
    (net (code "53") (name "Net-(IC2-VREG)") (class "Default")
      (node (ref "C8") (pin "1") (pinfunction "1_1") (pintype "passive"))
      (node (ref "IC2") (pin "8") (pinfunction "VREG_8") (pintype "passive"))
    )
    (net (code "54") (name "Net-(IC3-CP1)") (class "Default")
      (node (ref "C15") (pin "1") (pinfunction "1_1") (pintype "passive"))
      (node (ref "IC3") (pin "4") (pinfunction "CP1_4") (pintype "passive"))
    )
    (net (code "55") (name "Net-(IC3-CP2)") (class "Default")
      (node (ref "C15") (pin "2") (pinfunction "2_2") (pintype "passive"))
      (node (ref "IC3") (pin "5") (pinfunction "CP2_5") (pintype "passive"))
    )
    (net (code "56") (name "Net-(IC3-REF)") (class "Default")
      (node (ref "IC3") (pin "17") (pinfunction "REF_17") (pintype "input"))
      (node (ref "U5") (pin "WIPER") (pinfunction "2_WIPER") (pintype "bidirectional"))
    )
    (net (code "57") (name "Net-(IC3-RESET)") (class "Default")
      (node (ref "IC3") (pin "12") (pinfunction "RESET_12") (pintype "input"))
      (node (ref "IC3") (pin "14") (pinfunction "SLEEP_14") (pintype "input"))
      (node (ref "R11") (pin "1") (pinfunction "1_1") (pintype "passive"))
    )
    (net (code "58") (name "Net-(IC3-ROSC)") (class "Default")
      (node (ref "IC3") (pin "13") (pinfunction "ROSC_13") (pintype "input"))
      (node (ref "R14") (pin "2") (pinfunction "2_2") (pintype "passive"))
    )
    (net (code "59") (name "Net-(IC3-SENSE1)") (class "Default")
      (node (ref "IC3") (pin "23") (pinfunction "SENSE1_23") (pintype "input"))
      (node (ref "R12") (pin "1") (pinfunction "1_1") (pintype "passive"))
    )
    (net (code "60") (name "Net-(IC3-SENSE2)") (class "Default")
      (node (ref "IC3") (pin "27") (pinfunction "SENSE2_27") (pintype "input"))
      (node (ref "R13") (pin "1") (pinfunction "1_1") (pintype "passive"))
    )
    (net (code "61") (name "Net-(IC3-VREG)") (class "Default")
      (node (ref "C13") (pin "1") (pinfunction "1_1") (pintype "passive"))
      (node (ref "IC3") (pin "8") (pinfunction "VREG_8") (pintype "passive"))
    )
    (net (code "62") (name "Net-(LED1-PadA)") (class "Default")
      (node (ref "LED1") (pin "A") (pinfunction "A_A") (pintype "passive"))
      (node (ref "R16") (pin "1") (pinfunction "1_1") (pintype "passive"))
    )
    (net (code "63") (name "Net-(LED1-PadC)") (class "Default")
      (node (ref "LED1") (pin "C") (pinfunction "C_C") (pintype "passive"))
      (node (ref "S2") (pin "4") (pinfunction "4_4") (pintype "passive"))
    )
    (net (code "64") (name "Net-(LED2-PadA)") (class "Default")
      (node (ref "LED2") (pin "A") (pinfunction "A_A") (pintype "passive"))
      (node (ref "R17") (pin "1") (pinfunction "1_1") (pintype "passive"))
    )
    (net (code "65") (name "Net-(LED2-PadC)") (class "Default")
      (node (ref "LED2") (pin "C") (pinfunction "C_C") (pintype "passive"))
      (node (ref "S2") (pin "3") (pinfunction "3_3") (pintype "passive"))
    )
    (net (code "66") (name "Net-(LED3-PadA)") (class "Default")
      (node (ref "LED3") (pin "A") (pinfunction "A_A") (pintype "passive"))
      (node (ref "R18") (pin "1") (pinfunction "1_1") (pintype "passive"))
    )
    (net (code "67") (name "Net-(LED3-PadC)") (class "Default")
      (node (ref "LED3") (pin "C") (pinfunction "C_C") (pintype "passive"))
      (node (ref "S3") (pin "4") (pinfunction "4_4") (pintype "passive"))
    )
    (net (code "68") (name "Net-(R3-Pad1)") (class "Default")
      (node (ref "R3") (pin "1") (pinfunction "1_1") (pintype "passive"))
      (node (ref "U1") (pin "3") (pinfunction "3_3") (pintype "bidirectional"))
    )
    (net (code "69") (name "Net-(R10-Pad1)") (class "Default")
      (node (ref "R10") (pin "1") (pinfunction "1_1") (pintype "passive"))
      (node (ref "U2") (pin "3") (pinfunction "3_3") (pintype "bidirectional"))
    )
    (net (code "70") (name "Net-(R15-Pad1)") (class "Default")
      (node (ref "R15") (pin "1") (pinfunction "1_1") (pintype "passive"))
      (node (ref "U5") (pin "3") (pinfunction "3_3") (pintype "bidirectional"))
    )
    (net (code "71") (name "unconnected-(IC1-NC-Pad7)") (class "Default")
      (node (ref "IC1") (pin "7") (pinfunction "NC_7") (pintype "no_connect"))
    )
    (net (code "72") (name "unconnected-(IC1-NC-Pad20)") (class "Default")
      (node (ref "IC1") (pin "20") (pinfunction "NC_20") (pintype "no_connect"))
    )
    (net (code "73") (name "unconnected-(IC1-NC-Pad25)") (class "Default")
      (node (ref "IC1") (pin "25") (pinfunction "NC_25") (pintype "no_connect"))
    )
    (net (code "74") (name "unconnected-(IC2-NC-Pad7)") (class "Default")
      (node (ref "IC2") (pin "7") (pinfunction "NC_7") (pintype "no_connect"))
    )
    (net (code "75") (name "unconnected-(IC2-NC-Pad20)") (class "Default")
      (node (ref "IC2") (pin "20") (pinfunction "NC_20") (pintype "no_connect"))
    )
    (net (code "76") (name "unconnected-(IC2-NC-Pad25)") (class "Default")
      (node (ref "IC2") (pin "25") (pinfunction "NC_25") (pintype "no_connect"))
    )
    (net (code "77") (name "unconnected-(IC3-NC-Pad7)") (class "Default")
      (node (ref "IC3") (pin "7") (pinfunction "NC_7") (pintype "no_connect"))
    )
    (net (code "78") (name "unconnected-(IC3-NC-Pad20)") (class "Default")
      (node (ref "IC3") (pin "20") (pinfunction "NC_20") (pintype "no_connect"))
    )
    (net (code "79") (name "unconnected-(IC3-NC-Pad25)") (class "Default")
      (node (ref "IC3") (pin "25") (pinfunction "NC_25") (pintype "no_connect"))
    )
    (net (code "80") (name "unconnected-(S1-4-PadP$2)") (class "Default")
      (node (ref "S1") (pin "P$2") (pinfunction "4_P$2") (pintype "passive"))
    )
    (net (code "81") (name "unconnected-(S3-Pad2)") (class "Default")
      (node (ref "S3") (pin "2") (pinfunction "2_2") (pintype "passive"))
    )
    (net (code "82") (name "unconnected-(S3-Pad3)") (class "Default")
      (node (ref "S3") (pin "3") (pinfunction "3_3") (pintype "passive"))
    )
  )
)
